# 100x75_BOB.net
KiCad netlist of a schematic drawn in EAGLE
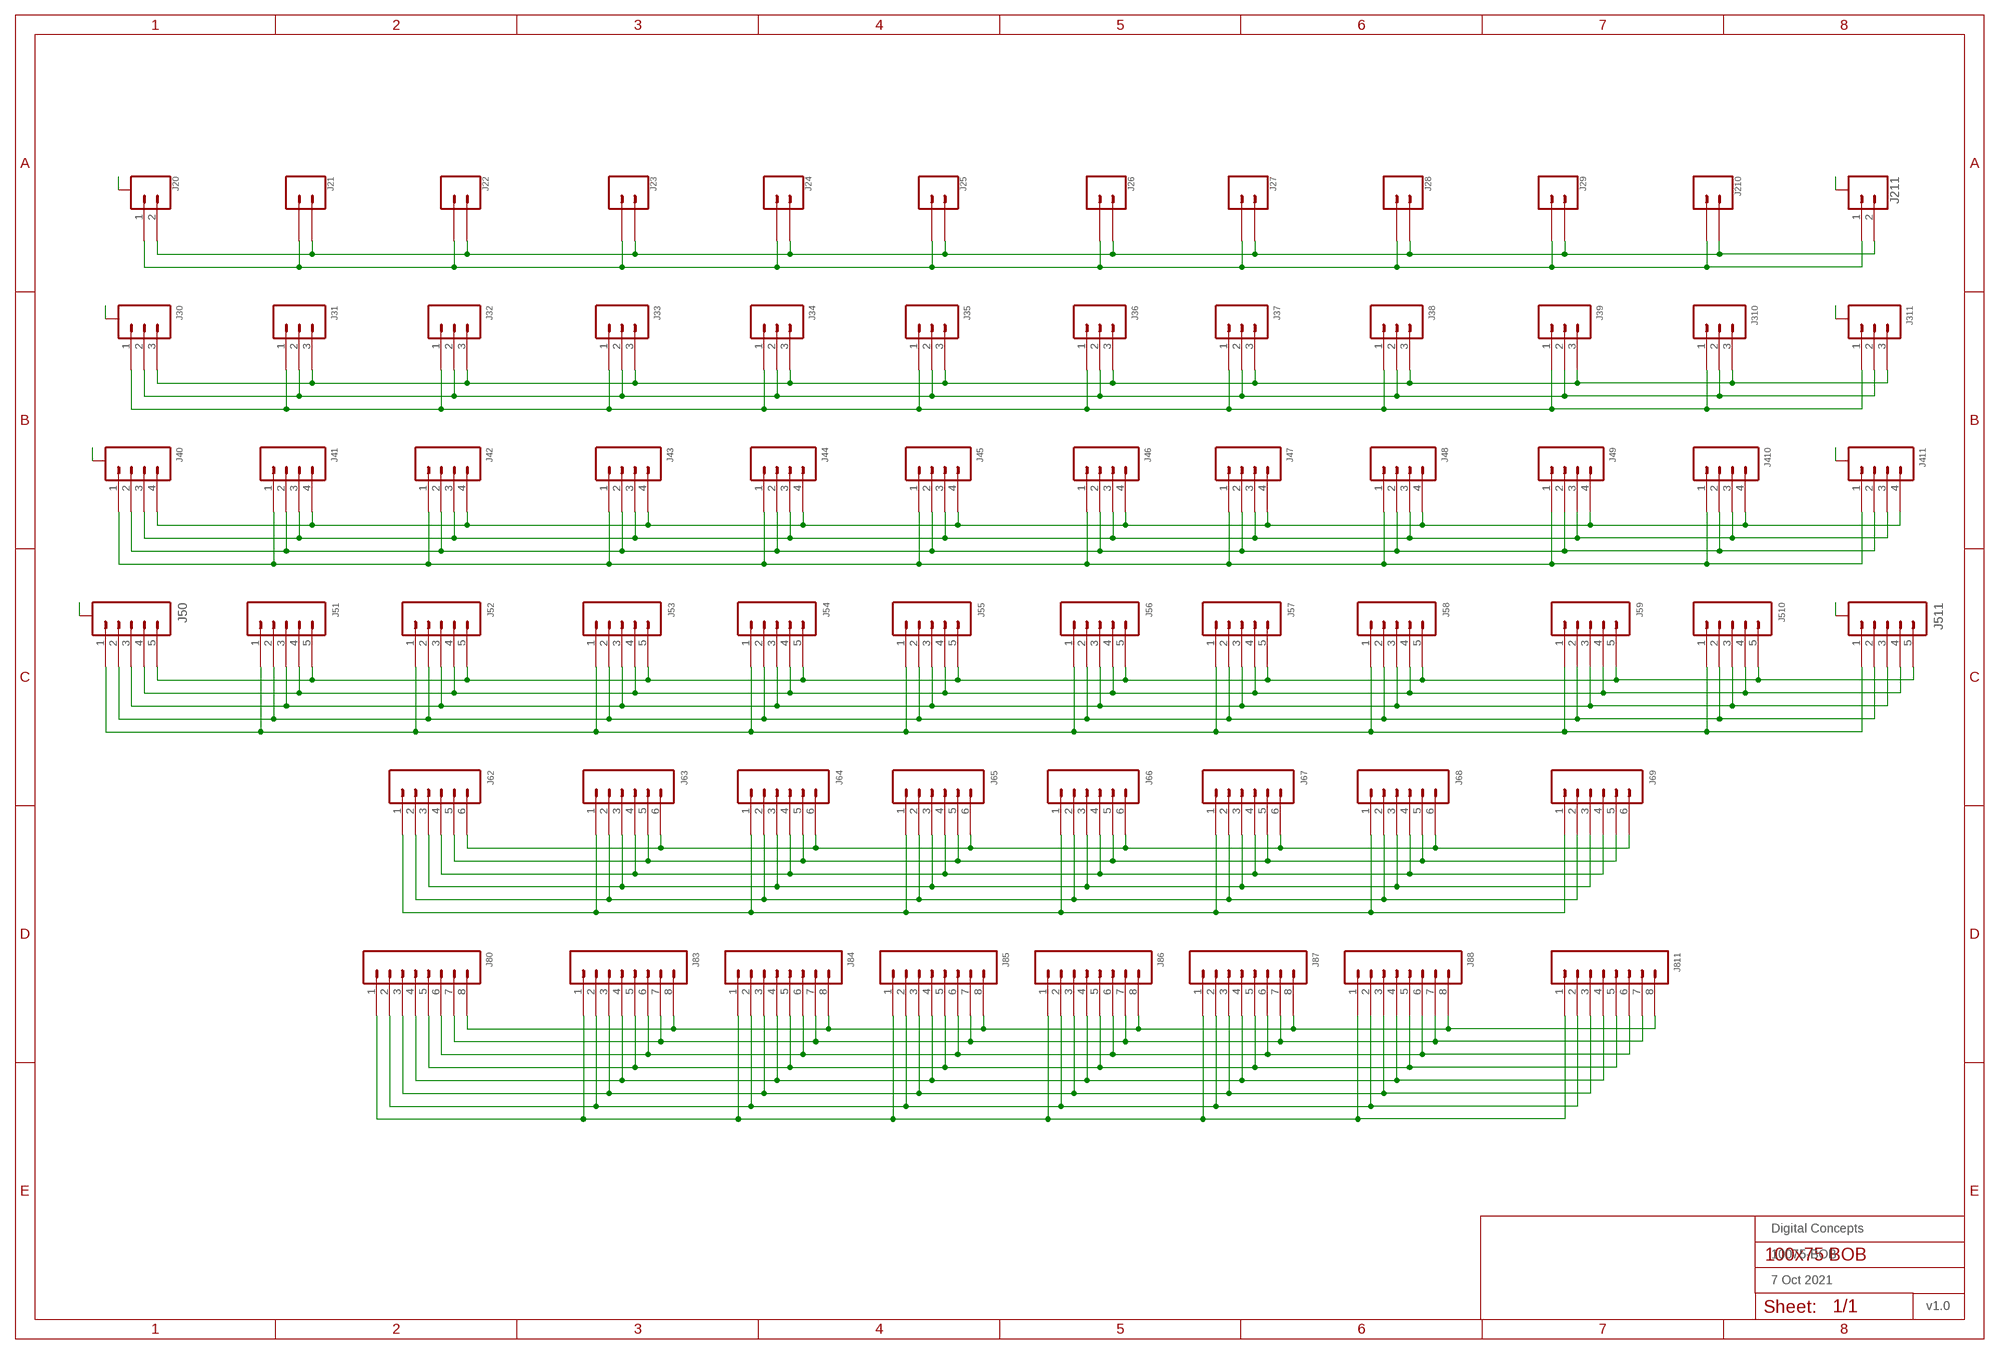
[diagram p0: schematic, sheet 1]

(export (version "E")
  (design (tool "Eeschema 10.0.6"))
  (components
    (comp (ref "J20")
      (value "JST-SH1.0-2-SMD-VERTICAL")
      (footprint "eagle-import:JST-SH1.0-2-VERTICAL")
      (libsource (lib "eagle-import") (part "JST-SH1.0-2-SMD-VERTICAL"))
    )
    (comp (ref "J21")
      (value "JST-GH1.25-2-VERTICAL")
      (footprint "eagle-import:JST-GH1.25-2-VERTICAL")
      (libsource (lib "eagle-import") (part "JST-GH1.25-2-VERTICAL"))
    )
    (comp (ref "J22")
      (value "JST-PH2.0-2-VERTICAL")
      (footprint "eagle-import:JST-PH2.0-2-VERTICAL")
      (libsource (lib "eagle-import") (part "JST-PH2.0-2-VERTICAL"))
    )
    (comp (ref "J23")
      (value "HEADER-1X2-GENERIC")
      (footprint "eagle-import:CONN_02-GENERIC")
      (libsource (lib "eagle-import") (part "HEADER-1X2-GENERIC"))
    )
    (comp (ref "J24")
      (value "HEADER-1X2-GENERIC")
      (footprint "eagle-import:CONN_02-GENERIC")
      (libsource (lib "eagle-import") (part "HEADER-1X2-GENERIC"))
    )
    (comp (ref "J25")
      (value "HEADER-1X2-GENERIC")
      (footprint "eagle-import:CONN_02-GENERIC")
      (libsource (lib "eagle-import") (part "HEADER-1X2-GENERIC"))
    )
    (comp (ref "J26")
      (value "HEADER-1X2-GENERIC")
      (footprint "eagle-import:CONN_02-GENERIC")
      (libsource (lib "eagle-import") (part "HEADER-1X2-GENERIC"))
    )
    (comp (ref "J27")
      (value "HEADER-1X2-GENERIC")
      (footprint "eagle-import:CONN_02-GENERIC")
      (libsource (lib "eagle-import") (part "HEADER-1X2-GENERIC"))
    )
    (comp (ref "J28")
      (value "HEADER-1X2-GENERIC")
      (footprint "eagle-import:CONN_02-GENERIC")
      (libsource (lib "eagle-import") (part "HEADER-1X2-GENERIC"))
    )
    (comp (ref "J29")
      (value "JST-PH2.0-2-VERTICAL")
      (footprint "eagle-import:JST-PH2.0-2-VERTICAL")
      (libsource (lib "eagle-import") (part "JST-PH2.0-2-VERTICAL"))
    )
    (comp (ref "J30")
      (value "JST-SH1.0-3-SMD-VERTICAL")
      (footprint "eagle-import:JST-SH1.0-3-VERTICAL")
      (libsource (lib "eagle-import") (part "JST-SH1.0-3-SMD-VERTICAL"))
    )
    (comp (ref "J31")
      (value "JST-GH1.25-3-VERTICAL")
      (footprint "eagle-import:JST-GH1.25-3-VERTICAL")
      (libsource (lib "eagle-import") (part "JST-GH1.25-3-VERTICAL"))
    )
    (comp (ref "J32")
      (value "JST-PH2.0-3-VERTICAL")
      (footprint "eagle-import:JST-PH2.0-3-VERTICAL")
      (libsource (lib "eagle-import") (part "JST-PH2.0-3-VERTICAL"))
    )
    (comp (ref "J33")
      (value "HEADER-1X3-GENERIC")
      (footprint "eagle-import:CONN_03-GENERIC")
      (libsource (lib "eagle-import") (part "HEADER-1X3-GENERIC"))
    )
    (comp (ref "J34")
      (value "HEADER-1X3-GENERIC")
      (footprint "eagle-import:CONN_03-GENERIC")
      (libsource (lib "eagle-import") (part "HEADER-1X3-GENERIC"))
    )
    (comp (ref "J35")
      (value "HEADER-1X3-GENERIC")
      (footprint "eagle-import:CONN_03-GENERIC")
      (libsource (lib "eagle-import") (part "HEADER-1X3-GENERIC"))
    )
    (comp (ref "J36")
      (value "HEADER-1X3-GENERIC")
      (footprint "eagle-import:CONN_03-GENERIC")
      (libsource (lib "eagle-import") (part "HEADER-1X3-GENERIC"))
    )
    (comp (ref "J37")
      (value "HEADER-1X3-GENERIC")
      (footprint "eagle-import:CONN_03-GENERIC")
      (libsource (lib "eagle-import") (part "HEADER-1X3-GENERIC"))
    )
    (comp (ref "J38")
      (value "HEADER-1X3-GENERIC")
      (footprint "eagle-import:CONN_03-GENERIC")
      (libsource (lib "eagle-import") (part "HEADER-1X3-GENERIC"))
    )
    (comp (ref "J39")
      (value "JST-PH2.0-3-VERTICAL")
      (footprint "eagle-import:JST-PH2.0-3-VERTICAL")
      (libsource (lib "eagle-import") (part "JST-PH2.0-3-VERTICAL"))
    )
    (comp (ref "J40")
      (value "JST-SH1.0-4-SMD-VERTICAL")
      (footprint "eagle-import:JST-SH1.0-4-VERTICAL")
      (libsource (lib "eagle-import") (part "JST-SH1.0-4-SMD-VERTICAL"))
    )
    (comp (ref "J41")
      (value "JST-GH1.25-4-VERTICAL")
      (footprint "eagle-import:JST-GH1.25-4-VERTICAL")
      (libsource (lib "eagle-import") (part "JST-GH1.25-4-VERTICAL"))
    )
    (comp (ref "J42")
      (value "JST-PH2.0-4-VERTICAL")
      (footprint "eagle-import:JST-PH2.0-4-VERTICAL")
      (libsource (lib "eagle-import") (part "JST-PH2.0-4-VERTICAL"))
    )
    (comp (ref "J43")
      (value "HEADER-1X4-GENERIC")
      (footprint "eagle-import:CONN_04-GENERIC")
      (libsource (lib "eagle-import") (part "HEADER-1X4-GENERIC"))
    )
    (comp (ref "J44")
      (value "HEADER-1X4-GENERIC")
      (footprint "eagle-import:CONN_04-GENERIC")
      (libsource (lib "eagle-import") (part "HEADER-1X4-GENERIC"))
    )
    (comp (ref "J45")
      (value "HEADER-1X4-GENERIC")
      (footprint "eagle-import:CONN_04-GENERIC")
      (libsource (lib "eagle-import") (part "HEADER-1X4-GENERIC"))
    )
    (comp (ref "J46")
      (value "HEADER-1X4-GENERIC")
      (footprint "eagle-import:CONN_04-GENERIC")
      (libsource (lib "eagle-import") (part "HEADER-1X4-GENERIC"))
    )
    (comp (ref "J47")
      (value "HEADER-1X4-GENERIC")
      (footprint "eagle-import:CONN_04-GENERIC")
      (libsource (lib "eagle-import") (part "HEADER-1X4-GENERIC"))
    )
    (comp (ref "J48")
      (value "HEADER-1X4-GENERIC")
      (footprint "eagle-import:CONN_04-GENERIC")
      (libsource (lib "eagle-import") (part "HEADER-1X4-GENERIC"))
    )
    (comp (ref "J49")
      (value "JST-PH2.0-4-VERTICAL")
      (footprint "eagle-import:JST-PH2.0-4-VERTICAL")
      (libsource (lib "eagle-import") (part "JST-PH2.0-4-VERTICAL"))
    )
    (comp (ref "J50")
      (value "JST-SH1.0-5-SMD-VERTICAL")
      (footprint "eagle-import:JST-SH1.0-5-VERTICAL")
      (libsource (lib "eagle-import") (part "JST-SH1.0-5-SMD-VERTICAL"))
    )
    (comp (ref "J51")
      (value "JST-GH1.25-5-VERTICAL")
      (footprint "eagle-import:JST-GH1.25-5-VERTICAL")
      (libsource (lib "eagle-import") (part "JST-GH1.25-5-VERTICAL"))
    )
    (comp (ref "J52")
      (value "JST-PH2.0-5-VERTICAL")
      (footprint "eagle-import:JST-PH2.0-5-VERTICAL")
      (libsource (lib "eagle-import") (part "JST-PH2.0-5-VERTICAL"))
    )
    (comp (ref "J53")
      (value "HEADER-1X5-GENERIC")
      (footprint "eagle-import:CONN_05-GENERIC")
      (libsource (lib "eagle-import") (part "HEADER-1X5-GENERIC"))
    )
    (comp (ref "J54")
      (value "HEADER-1X5-GENERIC")
      (footprint "eagle-import:CONN_05-GENERIC")
      (libsource (lib "eagle-import") (part "HEADER-1X5-GENERIC"))
    )
    (comp (ref "J55")
      (value "HEADER-1X5-GENERIC")
      (footprint "eagle-import:CONN_05-GENERIC")
      (libsource (lib "eagle-import") (part "HEADER-1X5-GENERIC"))
    )
    (comp (ref "J56")
      (value "HEADER-1X5-GENERIC")
      (footprint "eagle-import:CONN_05-GENERIC")
      (libsource (lib "eagle-import") (part "HEADER-1X5-GENERIC"))
    )
    (comp (ref "J57")
      (value "HEADER-1X5-GENERIC")
      (footprint "eagle-import:CONN_05-GENERIC")
      (libsource (lib "eagle-import") (part "HEADER-1X5-GENERIC"))
    )
    (comp (ref "J58")
      (value "HEADER-1X5-GENERIC")
      (footprint "eagle-import:CONN_05-GENERIC")
      (libsource (lib "eagle-import") (part "HEADER-1X5-GENERIC"))
    )
    (comp (ref "J59")
      (value "JST-PH2.0-5-VERTICAL")
      (footprint "eagle-import:JST-PH2.0-5-VERTICAL")
      (libsource (lib "eagle-import") (part "JST-PH2.0-5-VERTICAL"))
    )
    (comp (ref "J62")
      (value "RJ11-6P6C-VERTICAL")
      (footprint "eagle-import:RJ11-6-VERTICAL")
      (libsource (lib "eagle-import") (part "RJ11-6P6C-VERTICAL"))
    )
    (comp (ref "J63")
      (value "HEADER-1X6-GENERIC")
      (footprint "eagle-import:CONN_06-GENERIC")
      (libsource (lib "eagle-import") (part "HEADER-1X6-GENERIC"))
    )
    (comp (ref "J64")
      (value "HEADER-1X6-GENERIC")
      (footprint "eagle-import:CONN_06-GENERIC")
      (libsource (lib "eagle-import") (part "HEADER-1X6-GENERIC"))
    )
    (comp (ref "J65")
      (value "HEADER-1X6-GENERIC")
      (footprint "eagle-import:CONN_06-GENERIC")
      (libsource (lib "eagle-import") (part "HEADER-1X6-GENERIC"))
    )
    (comp (ref "J66")
      (value "HEADER-1X6-GENERIC")
      (footprint "eagle-import:CONN_06-GENERIC")
      (libsource (lib "eagle-import") (part "HEADER-1X6-GENERIC"))
    )
    (comp (ref "J67")
      (value "HEADER-1X6-GENERIC")
      (footprint "eagle-import:CONN_06-GENERIC")
      (libsource (lib "eagle-import") (part "HEADER-1X6-GENERIC"))
    )
    (comp (ref "J68")
      (value "HEADER-1X6-GENERIC")
      (footprint "eagle-import:CONN_06-GENERIC")
      (libsource (lib "eagle-import") (part "HEADER-1X6-GENERIC"))
    )
    (comp (ref "J69")
      (value "RJ11-6P6C-VERTICAL")
      (footprint "eagle-import:RJ11-6-VERTICAL")
      (libsource (lib "eagle-import") (part "RJ11-6P6C-VERTICAL"))
    )
    (comp (ref "J80")
      (value "RJ45-8P8C-VERTICAL")
      (footprint "eagle-import:RJ45-VERTICAL")
      (libsource (lib "eagle-import") (part "RJ45-8P8C-VERTICAL"))
    )
    (comp (ref "J83")
      (value "HEADER-1X8-GENERIC")
      (footprint "eagle-import:CONN_08-GENERIC")
      (libsource (lib "eagle-import") (part "HEADER-1X8-GENERIC"))
    )
    (comp (ref "J84")
      (value "HEADER-1X8-GENERIC")
      (footprint "eagle-import:CONN_08-GENERIC")
      (libsource (lib "eagle-import") (part "HEADER-1X8-GENERIC"))
    )
    (comp (ref "J85")
      (value "HEADER-1X8-GENERIC")
      (footprint "eagle-import:CONN_08-GENERIC")
      (libsource (lib "eagle-import") (part "HEADER-1X8-GENERIC"))
    )
    (comp (ref "J86")
      (value "HEADER-1X8-GENERIC")
      (footprint "eagle-import:CONN_08-GENERIC")
      (libsource (lib "eagle-import") (part "HEADER-1X8-GENERIC"))
    )
    (comp (ref "J87")
      (value "HEADER-1X8-GENERIC")
      (footprint "eagle-import:CONN_08-GENERIC")
      (libsource (lib "eagle-import") (part "HEADER-1X8-GENERIC"))
    )
    (comp (ref "J88")
      (value "HEADER-1X8-GENERIC")
      (footprint "eagle-import:CONN_08-GENERIC")
      (libsource (lib "eagle-import") (part "HEADER-1X8-GENERIC"))
    )
    (comp (ref "J210")
      (value "JST-GH1.25-2-VERTICAL")
      (footprint "eagle-import:JST-GH1.25-2-VERTICAL")
      (libsource (lib "eagle-import") (part "JST-GH1.25-2-VERTICAL"))
    )
    (comp (ref "J211")
      (value "JST-SH1.0-2-SMD-VERTICAL")
      (footprint "eagle-import:JST-SH1.0-2-VERTICAL")
      (libsource (lib "eagle-import") (part "JST-SH1.0-2-SMD-VERTICAL"))
    )
    (comp (ref "J310")
      (value "JST-GH1.25-3-VERTICAL")
      (footprint "eagle-import:JST-GH1.25-3-VERTICAL")
      (libsource (lib "eagle-import") (part "JST-GH1.25-3-VERTICAL"))
    )
    (comp (ref "J311")
      (value "JST-SH1.0-3-SMD-VERTICAL")
      (footprint "eagle-import:JST-SH1.0-3-VERTICAL")
      (libsource (lib "eagle-import") (part "JST-SH1.0-3-SMD-VERTICAL"))
    )
    (comp (ref "J410")
      (value "JST-GH1.25-4-VERTICAL")
      (footprint "eagle-import:JST-GH1.25-4-VERTICAL")
      (libsource (lib "eagle-import") (part "JST-GH1.25-4-VERTICAL"))
    )
    (comp (ref "J411")
      (value "JST-SH1.0-4-SMD-VERTICAL")
      (footprint "eagle-import:JST-SH1.0-4-VERTICAL")
      (libsource (lib "eagle-import") (part "JST-SH1.0-4-SMD-VERTICAL"))
    )
    (comp (ref "J510")
      (value "JST-GH1.25-5-VERTICAL")
      (footprint "eagle-import:JST-GH1.25-5-VERTICAL")
      (libsource (lib "eagle-import") (part "JST-GH1.25-5-VERTICAL"))
    )
    (comp (ref "J511")
      (value "JST-SH1.0-5-SMD-VERTICAL")
      (footprint "eagle-import:JST-SH1.0-5-VERTICAL")
      (libsource (lib "eagle-import") (part "JST-SH1.0-5-SMD-VERTICAL"))
    )
    (comp (ref "J811")
      (value "RJ45-8P8C-VERTICAL")
      (footprint "eagle-import:RJ45-VERTICAL")
      (libsource (lib "eagle-import") (part "RJ45-8P8C-VERTICAL"))
    )
  )
  (nets
    (net (code "1") (name "/A") (class "Default")
      (node (ref "J20") (pin "A@1") (pinfunction "A_A@1") (pintype "power_in"))
      (node (ref "J20") (pin "A@2") (pinfunction "A_A@2") (pintype "power_in"))
      (node (ref "J211") (pin "A@1") (pinfunction "A_A@1") (pintype "power_in"))
      (node (ref "J211") (pin "A@2") (pinfunction "A_A@2") (pintype "power_in"))
      (node (ref "J30") (pin "A@1") (pinfunction "A_A@1") (pintype "power_in"))
      (node (ref "J30") (pin "A@3") (pinfunction "A_A@3") (pintype "power_in"))
      (node (ref "J311") (pin "A@1") (pinfunction "A_A@1") (pintype "power_in"))
      (node (ref "J311") (pin "A@3") (pinfunction "A_A@3") (pintype "power_in"))
      (node (ref "J40") (pin "A@1") (pinfunction "A_A@1") (pintype "power_in"))
      (node (ref "J40") (pin "A@4") (pinfunction "A_A@4") (pintype "power_in"))
      (node (ref "J411") (pin "A@1") (pinfunction "A_A@1") (pintype "power_in"))
      (node (ref "J411") (pin "A@4") (pinfunction "A_A@4") (pintype "power_in"))
      (node (ref "J50") (pin "A@1") (pinfunction "A_A@1") (pintype "power_in"))
      (node (ref "J50") (pin "A@5") (pinfunction "A_A@5") (pintype "power_in"))
      (node (ref "J511") (pin "A@1") (pinfunction "A_A@1") (pintype "power_in"))
      (node (ref "J511") (pin "A@5") (pinfunction "A_A@5") (pintype "power_in"))
    )
    (net (code "2") (name "Net-(J20-Pad1)") (class "Default")
      (node (ref "J20") (pin "1") (pinfunction "1_1") (pintype "passive"))
      (node (ref "J21") (pin "1") (pinfunction "1_1") (pintype "passive"))
      (node (ref "J210") (pin "1") (pinfunction "1_1") (pintype "passive"))
      (node (ref "J211") (pin "1") (pinfunction "1_1") (pintype "passive"))
      (node (ref "J22") (pin "1") (pinfunction "1_1") (pintype "passive"))
      (node (ref "J23") (pin "1") (pinfunction "1_1") (pintype "passive"))
      (node (ref "J24") (pin "1") (pinfunction "1_1") (pintype "passive"))
      (node (ref "J25") (pin "1") (pinfunction "1_1") (pintype "passive"))
      (node (ref "J26") (pin "1") (pinfunction "1_1") (pintype "passive"))
      (node (ref "J27") (pin "1") (pinfunction "1_1") (pintype "passive"))
      (node (ref "J28") (pin "1") (pinfunction "1_1") (pintype "passive"))
      (node (ref "J29") (pin "1") (pinfunction "1_1") (pintype "passive"))
    )
    (net (code "3") (name "Net-(J20-Pad2)") (class "Default")
      (node (ref "J20") (pin "2") (pinfunction "2_2") (pintype "passive"))
      (node (ref "J21") (pin "2") (pinfunction "2_2") (pintype "passive"))
      (node (ref "J210") (pin "2") (pinfunction "2_2") (pintype "passive"))
      (node (ref "J211") (pin "2") (pinfunction "2_2") (pintype "passive"))
      (node (ref "J22") (pin "2") (pinfunction "2_2") (pintype "passive"))
      (node (ref "J23") (pin "2") (pinfunction "2_2") (pintype "passive"))
      (node (ref "J24") (pin "2") (pinfunction "2_2") (pintype "passive"))
      (node (ref "J25") (pin "2") (pinfunction "2_2") (pintype "passive"))
      (node (ref "J26") (pin "2") (pinfunction "2_2") (pintype "passive"))
      (node (ref "J27") (pin "2") (pinfunction "2_2") (pintype "passive"))
      (node (ref "J28") (pin "2") (pinfunction "2_2") (pintype "passive"))
      (node (ref "J29") (pin "2") (pinfunction "2_2") (pintype "passive"))
    )
    (net (code "4") (name "Net-(J30-Pad1)") (class "Default")
      (node (ref "J30") (pin "1") (pinfunction "1_1") (pintype "passive"))
      (node (ref "J31") (pin "1") (pinfunction "1_1") (pintype "passive"))
      (node (ref "J310") (pin "1") (pinfunction "1_1") (pintype "passive"))
      (node (ref "J311") (pin "1") (pinfunction "1_1") (pintype "passive"))
      (node (ref "J32") (pin "1") (pinfunction "1_1") (pintype "passive"))
      (node (ref "J33") (pin "1") (pinfunction "1_1") (pintype "passive"))
      (node (ref "J34") (pin "1") (pinfunction "1_1") (pintype "passive"))
      (node (ref "J35") (pin "1") (pinfunction "1_1") (pintype "passive"))
      (node (ref "J36") (pin "1") (pinfunction "1_1") (pintype "passive"))
      (node (ref "J37") (pin "1") (pinfunction "1_1") (pintype "passive"))
      (node (ref "J38") (pin "1") (pinfunction "1_1") (pintype "passive"))
      (node (ref "J39") (pin "1") (pinfunction "1_1") (pintype "passive"))
    )
    (net (code "5") (name "Net-(J30-Pad2)") (class "Default")
      (node (ref "J30") (pin "2") (pinfunction "2_2") (pintype "passive"))
      (node (ref "J31") (pin "2") (pinfunction "2_2") (pintype "passive"))
      (node (ref "J310") (pin "2") (pinfunction "2_2") (pintype "passive"))
      (node (ref "J311") (pin "2") (pinfunction "2_2") (pintype "passive"))
      (node (ref "J32") (pin "2") (pinfunction "2_2") (pintype "passive"))
      (node (ref "J33") (pin "2") (pinfunction "2_2") (pintype "passive"))
      (node (ref "J34") (pin "2") (pinfunction "2_2") (pintype "passive"))
      (node (ref "J35") (pin "2") (pinfunction "2_2") (pintype "passive"))
      (node (ref "J36") (pin "2") (pinfunction "2_2") (pintype "passive"))
      (node (ref "J37") (pin "2") (pinfunction "2_2") (pintype "passive"))
      (node (ref "J38") (pin "2") (pinfunction "2_2") (pintype "passive"))
      (node (ref "J39") (pin "2") (pinfunction "2_2") (pintype "passive"))
    )
    (net (code "6") (name "Net-(J30-Pad3)") (class "Default")
      (node (ref "J30") (pin "3") (pinfunction "3_3") (pintype "passive"))
      (node (ref "J31") (pin "3") (pinfunction "3_3") (pintype "passive"))
      (node (ref "J310") (pin "3") (pinfunction "3_3") (pintype "passive"))
      (node (ref "J311") (pin "3") (pinfunction "3_3") (pintype "passive"))
      (node (ref "J32") (pin "3") (pinfunction "3_3") (pintype "passive"))
      (node (ref "J33") (pin "3") (pinfunction "3_3") (pintype "passive"))
      (node (ref "J34") (pin "3") (pinfunction "3_3") (pintype "passive"))
      (node (ref "J35") (pin "3") (pinfunction "3_3") (pintype "passive"))
      (node (ref "J36") (pin "3") (pinfunction "3_3") (pintype "passive"))
      (node (ref "J37") (pin "3") (pinfunction "3_3") (pintype "passive"))
      (node (ref "J38") (pin "3") (pinfunction "3_3") (pintype "passive"))
      (node (ref "J39") (pin "3") (pinfunction "3_3") (pintype "passive"))
    )
    (net (code "7") (name "Net-(J40-Pad1)") (class "Default")
      (node (ref "J40") (pin "1") (pinfunction "1_1") (pintype "passive"))
      (node (ref "J41") (pin "1") (pinfunction "1_1") (pintype "passive"))
      (node (ref "J410") (pin "1") (pinfunction "1_1") (pintype "passive"))
      (node (ref "J411") (pin "1") (pinfunction "1_1") (pintype "passive"))
      (node (ref "J42") (pin "1") (pinfunction "1_1") (pintype "passive"))
      (node (ref "J43") (pin "1") (pinfunction "1_1") (pintype "passive"))
      (node (ref "J44") (pin "1") (pinfunction "1_1") (pintype "passive"))
      (node (ref "J45") (pin "1") (pinfunction "1_1") (pintype "passive"))
      (node (ref "J46") (pin "1") (pinfunction "1_1") (pintype "passive"))
      (node (ref "J47") (pin "1") (pinfunction "1_1") (pintype "passive"))
      (node (ref "J48") (pin "1") (pinfunction "1_1") (pintype "passive"))
      (node (ref "J49") (pin "1") (pinfunction "1_1") (pintype "passive"))
    )
    (net (code "8") (name "Net-(J40-Pad2)") (class "Default")
      (node (ref "J40") (pin "2") (pinfunction "2_2") (pintype "passive"))
      (node (ref "J41") (pin "2") (pinfunction "2_2") (pintype "passive"))
      (node (ref "J410") (pin "2") (pinfunction "2_2") (pintype "passive"))
      (node (ref "J411") (pin "2") (pinfunction "2_2") (pintype "passive"))
      (node (ref "J42") (pin "2") (pinfunction "2_2") (pintype "passive"))
      (node (ref "J43") (pin "2") (pinfunction "2_2") (pintype "passive"))
      (node (ref "J44") (pin "2") (pinfunction "2_2") (pintype "passive"))
      (node (ref "J45") (pin "2") (pinfunction "2_2") (pintype "passive"))
      (node (ref "J46") (pin "2") (pinfunction "2_2") (pintype "passive"))
      (node (ref "J47") (pin "2") (pinfunction "2_2") (pintype "passive"))
      (node (ref "J48") (pin "2") (pinfunction "2_2") (pintype "passive"))
      (node (ref "J49") (pin "2") (pinfunction "2_2") (pintype "passive"))
    )
    (net (code "9") (name "Net-(J40-Pad3)") (class "Default")
      (node (ref "J40") (pin "3") (pinfunction "3_3") (pintype "passive"))
      (node (ref "J41") (pin "3") (pinfunction "3_3") (pintype "passive"))
      (node (ref "J410") (pin "3") (pinfunction "3_3") (pintype "passive"))
      (node (ref "J411") (pin "3") (pinfunction "3_3") (pintype "passive"))
      (node (ref "J42") (pin "3") (pinfunction "3_3") (pintype "passive"))
      (node (ref "J43") (pin "3") (pinfunction "3_3") (pintype "passive"))
      (node (ref "J44") (pin "3") (pinfunction "3_3") (pintype "passive"))
      (node (ref "J45") (pin "3") (pinfunction "3_3") (pintype "passive"))
      (node (ref "J46") (pin "3") (pinfunction "3_3") (pintype "passive"))
      (node (ref "J47") (pin "3") (pinfunction "3_3") (pintype "passive"))
      (node (ref "J48") (pin "3") (pinfunction "3_3") (pintype "passive"))
      (node (ref "J49") (pin "3") (pinfunction "3_3") (pintype "passive"))
    )
    (net (code "10") (name "Net-(J40-Pad4)") (class "Default")
      (node (ref "J40") (pin "4") (pinfunction "4_4") (pintype "passive"))
      (node (ref "J41") (pin "4") (pinfunction "4_4") (pintype "passive"))
      (node (ref "J410") (pin "4") (pinfunction "4_4") (pintype "passive"))
      (node (ref "J411") (pin "4") (pinfunction "4_4") (pintype "passive"))
      (node (ref "J42") (pin "4") (pinfunction "4_4") (pintype "passive"))
      (node (ref "J43") (pin "4") (pinfunction "4_4") (pintype "passive"))
      (node (ref "J44") (pin "4") (pinfunction "4_4") (pintype "passive"))
      (node (ref "J45") (pin "4") (pinfunction "4_4") (pintype "passive"))
      (node (ref "J46") (pin "4") (pinfunction "4_4") (pintype "passive"))
      (node (ref "J47") (pin "4") (pinfunction "4_4") (pintype "passive"))
      (node (ref "J48") (pin "4") (pinfunction "4_4") (pintype "passive"))
      (node (ref "J49") (pin "4") (pinfunction "4_4") (pintype "passive"))
    )
    (net (code "11") (name "Net-(J50-Pad1)") (class "Default")
      (node (ref "J50") (pin "1") (pinfunction "1_1") (pintype "passive"))
      (node (ref "J51") (pin "1") (pinfunction "1_1") (pintype "passive"))
      (node (ref "J510") (pin "1") (pinfunction "1_1") (pintype "passive"))
      (node (ref "J511") (pin "1") (pinfunction "1_1") (pintype "passive"))
      (node (ref "J52") (pin "1") (pinfunction "1_1") (pintype "passive"))
      (node (ref "J53") (pin "1") (pinfunction "1_1") (pintype "passive"))
      (node (ref "J54") (pin "1") (pinfunction "1_1") (pintype "passive"))
      (node (ref "J55") (pin "1") (pinfunction "1_1") (pintype "passive"))
      (node (ref "J56") (pin "1") (pinfunction "1_1") (pintype "passive"))
      (node (ref "J57") (pin "1") (pinfunction "1_1") (pintype "passive"))
      (node (ref "J58") (pin "1") (pinfunction "1_1") (pintype "passive"))
      (node (ref "J59") (pin "1") (pinfunction "1_1") (pintype "passive"))
    )
    (net (code "12") (name "Net-(J50-Pad2)") (class "Default")
      (node (ref "J50") (pin "2") (pinfunction "2_2") (pintype "passive"))
      (node (ref "J51") (pin "2") (pinfunction "2_2") (pintype "passive"))
      (node (ref "J510") (pin "2") (pinfunction "2_2") (pintype "passive"))
      (node (ref "J511") (pin "2") (pinfunction "2_2") (pintype "passive"))
      (node (ref "J52") (pin "2") (pinfunction "2_2") (pintype "passive"))
      (node (ref "J53") (pin "2") (pinfunction "2_2") (pintype "passive"))
      (node (ref "J54") (pin "2") (pinfunction "2_2") (pintype "passive"))
      (node (ref "J55") (pin "2") (pinfunction "2_2") (pintype "passive"))
      (node (ref "J56") (pin "2") (pinfunction "2_2") (pintype "passive"))
      (node (ref "J57") (pin "2") (pinfunction "2_2") (pintype "passive"))
      (node (ref "J58") (pin "2") (pinfunction "2_2") (pintype "passive"))
      (node (ref "J59") (pin "2") (pinfunction "2_2") (pintype "passive"))
    )
    (net (code "13") (name "Net-(J50-Pad3)") (class "Default")
      (node (ref "J50") (pin "3") (pinfunction "3_3") (pintype "passive"))
      (node (ref "J51") (pin "3") (pinfunction "3_3") (pintype "passive"))
      (node (ref "J510") (pin "3") (pinfunction "3_3") (pintype "passive"))
      (node (ref "J511") (pin "3") (pinfunction "3_3") (pintype "passive"))
      (node (ref "J52") (pin "3") (pinfunction "3_3") (pintype "passive"))
      (node (ref "J53") (pin "3") (pinfunction "3_3") (pintype "passive"))
      (node (ref "J54") (pin "3") (pinfunction "3_3") (pintype "passive"))
      (node (ref "J55") (pin "3") (pinfunction "3_3") (pintype "passive"))
      (node (ref "J56") (pin "3") (pinfunction "3_3") (pintype "passive"))
      (node (ref "J57") (pin "3") (pinfunction "3_3") (pintype "passive"))
      (node (ref "J58") (pin "3") (pinfunction "3_3") (pintype "passive"))
      (node (ref "J59") (pin "3") (pinfunction "3_3") (pintype "passive"))
    )
    (net (code "14") (name "Net-(J50-Pad4)") (class "Default")
      (node (ref "J50") (pin "4") (pinfunction "4_4") (pintype "passive"))
      (node (ref "J51") (pin "4") (pinfunction "4_4") (pintype "passive"))
      (node (ref "J510") (pin "4") (pinfunction "4_4") (pintype "passive"))
      (node (ref "J511") (pin "4") (pinfunction "4_4") (pintype "passive"))
      (node (ref "J52") (pin "4") (pinfunction "4_4") (pintype "passive"))
      (node (ref "J53") (pin "4") (pinfunction "4_4") (pintype "passive"))
      (node (ref "J54") (pin "4") (pinfunction "4_4") (pintype "passive"))
      (node (ref "J55") (pin "4") (pinfunction "4_4") (pintype "passive"))
      (node (ref "J56") (pin "4") (pinfunction "4_4") (pintype "passive"))
      (node (ref "J57") (pin "4") (pinfunction "4_4") (pintype "passive"))
      (node (ref "J58") (pin "4") (pinfunction "4_4") (pintype "passive"))
      (node (ref "J59") (pin "4") (pinfunction "4_4") (pintype "passive"))
    )
    (net (code "15") (name "Net-(J50-Pad5)") (class "Default")
      (node (ref "J50") (pin "5") (pinfunction "5_5") (pintype "passive"))
      (node (ref "J51") (pin "5") (pinfunction "5_5") (pintype "passive"))
      (node (ref "J510") (pin "5") (pinfunction "5_5") (pintype "passive"))
      (node (ref "J511") (pin "5") (pinfunction "5_5") (pintype "passive"))
      (node (ref "J52") (pin "5") (pinfunction "5_5") (pintype "passive"))
      (node (ref "J53") (pin "5") (pinfunction "5_5") (pintype "passive"))
      (node (ref "J54") (pin "5") (pinfunction "5_5") (pintype "passive"))
      (node (ref "J55") (pin "5") (pinfunction "5_5") (pintype "passive"))
      (node (ref "J56") (pin "5") (pinfunction "5_5") (pintype "passive"))
      (node (ref "J57") (pin "5") (pinfunction "5_5") (pintype "passive"))
      (node (ref "J58") (pin "5") (pinfunction "5_5") (pintype "passive"))
      (node (ref "J59") (pin "5") (pinfunction "5_5") (pintype "passive"))
    )
    (net (code "16") (name "Net-(J62-Pad1)") (class "Default")
      (node (ref "J62") (pin "1") (pinfunction "1_1") (pintype "passive"))
      (node (ref "J63") (pin "1") (pinfunction "1_1") (pintype "passive"))
      (node (ref "J64") (pin "1") (pinfunction "1_1") (pintype "passive"))
      (node (ref "J65") (pin "1") (pinfunction "1_1") (pintype "passive"))
      (node (ref "J66") (pin "1") (pinfunction "1_1") (pintype "passive"))
      (node (ref "J67") (pin "1") (pinfunction "1_1") (pintype "passive"))
      (node (ref "J68") (pin "1") (pinfunction "1_1") (pintype "passive"))
      (node (ref "J69") (pin "1") (pinfunction "1_1") (pintype "passive"))
    )
    (net (code "17") (name "Net-(J62-Pad2)") (class "Default")
      (node (ref "J62") (pin "2") (pinfunction "2_2") (pintype "passive"))
      (node (ref "J63") (pin "2") (pinfunction "2_2") (pintype "passive"))
      (node (ref "J64") (pin "2") (pinfunction "2_2") (pintype "passive"))
      (node (ref "J65") (pin "2") (pinfunction "2_2") (pintype "passive"))
      (node (ref "J66") (pin "2") (pinfunction "2_2") (pintype "passive"))
      (node (ref "J67") (pin "2") (pinfunction "2_2") (pintype "passive"))
      (node (ref "J68") (pin "2") (pinfunction "2_2") (pintype "passive"))
      (node (ref "J69") (pin "2") (pinfunction "2_2") (pintype "passive"))
    )
    (net (code "18") (name "Net-(J62-Pad3)") (class "Default")
      (node (ref "J62") (pin "3") (pinfunction "3_3") (pintype "passive"))
      (node (ref "J63") (pin "3") (pinfunction "3_3") (pintype "passive"))
      (node (ref "J64") (pin "3") (pinfunction "3_3") (pintype "passive"))
      (node (ref "J65") (pin "3") (pinfunction "3_3") (pintype "passive"))
      (node (ref "J66") (pin "3") (pinfunction "3_3") (pintype "passive"))
      (node (ref "J67") (pin "3") (pinfunction "3_3") (pintype "passive"))
      (node (ref "J68") (pin "3") (pinfunction "3_3") (pintype "passive"))
      (node (ref "J69") (pin "3") (pinfunction "3_3") (pintype "passive"))
    )
    (net (code "19") (name "Net-(J62-Pad4)") (class "Default")
      (node (ref "J62") (pin "4") (pinfunction "4_4") (pintype "passive"))
      (node (ref "J63") (pin "4") (pinfunction "4_4") (pintype "passive"))
      (node (ref "J64") (pin "4") (pinfunction "4_4") (pintype "passive"))
      (node (ref "J65") (pin "4") (pinfunction "4_4") (pintype "passive"))
      (node (ref "J66") (pin "4") (pinfunction "4_4") (pintype "passive"))
      (node (ref "J67") (pin "4") (pinfunction "4_4") (pintype "passive"))
      (node (ref "J68") (pin "4") (pinfunction "4_4") (pintype "passive"))
      (node (ref "J69") (pin "4") (pinfunction "4_4") (pintype "passive"))
    )
    (net (code "20") (name "Net-(J62-Pad5)") (class "Default")
      (node (ref "J62") (pin "5") (pinfunction "5_5") (pintype "passive"))
      (node (ref "J63") (pin "5") (pinfunction "5_5") (pintype "passive"))
      (node (ref "J64") (pin "5") (pinfunction "5_5") (pintype "passive"))
      (node (ref "J65") (pin "5") (pinfunction "5_5") (pintype "passive"))
      (node (ref "J66") (pin "5") (pinfunction "5_5") (pintype "passive"))
      (node (ref "J67") (pin "5") (pinfunction "5_5") (pintype "passive"))
      (node (ref "J68") (pin "5") (pinfunction "5_5") (pintype "passive"))
      (node (ref "J69") (pin "5") (pinfunction "5_5") (pintype "passive"))
    )
    (net (code "21") (name "Net-(J62-Pad6)") (class "Default")
      (node (ref "J62") (pin "6") (pinfunction "6_6") (pintype "passive"))
      (node (ref "J63") (pin "6") (pinfunction "6_6") (pintype "passive"))
      (node (ref "J64") (pin "6") (pinfunction "6_6") (pintype "passive"))
      (node (ref "J65") (pin "6") (pinfunction "6_6") (pintype "passive"))
      (node (ref "J66") (pin "6") (pinfunction "6_6") (pintype "passive"))
      (node (ref "J67") (pin "6") (pinfunction "6_6") (pintype "passive"))
      (node (ref "J68") (pin "6") (pinfunction "6_6") (pintype "passive"))
      (node (ref "J69") (pin "6") (pinfunction "6_6") (pintype "passive"))
    )
    (net (code "22") (name "Net-(J80-Pad1)") (class "Default")
      (node (ref "J80") (pin "1") (pinfunction "1_1") (pintype "passive"))
      (node (ref "J811") (pin "1") (pinfunction "1_1") (pintype "passive"))
      (node (ref "J83") (pin "1") (pinfunction "1_1") (pintype "passive"))
      (node (ref "J84") (pin "1") (pinfunction "1_1") (pintype "passive"))
      (node (ref "J85") (pin "1") (pinfunction "1_1") (pintype "passive"))
      (node (ref "J86") (pin "1") (pinfunction "1_1") (pintype "passive"))
      (node (ref "J87") (pin "1") (pinfunction "1_1") (pintype "passive"))
      (node (ref "J88") (pin "1") (pinfunction "1_1") (pintype "passive"))
    )
    (net (code "23") (name "Net-(J80-Pad2)") (class "Default")
      (node (ref "J80") (pin "2") (pinfunction "2_2") (pintype "passive"))
      (node (ref "J811") (pin "2") (pinfunction "2_2") (pintype "passive"))
      (node (ref "J83") (pin "2") (pinfunction "2_2") (pintype "passive"))
      (node (ref "J84") (pin "2") (pinfunction "2_2") (pintype "passive"))
      (node (ref "J85") (pin "2") (pinfunction "2_2") (pintype "passive"))
      (node (ref "J86") (pin "2") (pinfunction "2_2") (pintype "passive"))
      (node (ref "J87") (pin "2") (pinfunction "2_2") (pintype "passive"))
      (node (ref "J88") (pin "2") (pinfunction "2_2") (pintype "passive"))
    )
    (net (code "24") (name "Net-(J80-Pad3)") (class "Default")
      (node (ref "J80") (pin "3") (pinfunction "3_3") (pintype "passive"))
      (node (ref "J811") (pin "3") (pinfunction "3_3") (pintype "passive"))
      (node (ref "J83") (pin "3") (pinfunction "3_3") (pintype "passive"))
      (node (ref "J84") (pin "3") (pinfunction "3_3") (pintype "passive"))
      (node (ref "J85") (pin "3") (pinfunction "3_3") (pintype "passive"))
      (node (ref "J86") (pin "3") (pinfunction "3_3") (pintype "passive"))
      (node (ref "J87") (pin "3") (pinfunction "3_3") (pintype "passive"))
      (node (ref "J88") (pin "3") (pinfunction "3_3") (pintype "passive"))
    )
    (net (code "25") (name "Net-(J80-Pad4)") (class "Default")
      (node (ref "J80") (pin "4") (pinfunction "4_4") (pintype "passive"))
      (node (ref "J811") (pin "4") (pinfunction "4_4") (pintype "passive"))
      (node (ref "J83") (pin "4") (pinfunction "4_4") (pintype "passive"))
      (node (ref "J84") (pin "4") (pinfunction "4_4") (pintype "passive"))
      (node (ref "J85") (pin "4") (pinfunction "4_4") (pintype "passive"))
      (node (ref "J86") (pin "4") (pinfunction "4_4") (pintype "passive"))
      (node (ref "J87") (pin "4") (pinfunction "4_4") (pintype "passive"))
      (node (ref "J88") (pin "4") (pinfunction "4_4") (pintype "passive"))
    )
    (net (code "26") (name "Net-(J80-Pad5)") (class "Default")
      (node (ref "J80") (pin "5") (pinfunction "5_5") (pintype "passive"))
      (node (ref "J811") (pin "5") (pinfunction "5_5") (pintype "passive"))
      (node (ref "J83") (pin "5") (pinfunction "5_5") (pintype "passive"))
      (node (ref "J84") (pin "5") (pinfunction "5_5") (pintype "passive"))
      (node (ref "J85") (pin "5") (pinfunction "5_5") (pintype "passive"))
      (node (ref "J86") (pin "5") (pinfunction "5_5") (pintype "passive"))
      (node (ref "J87") (pin "5") (pinfunction "5_5") (pintype "passive"))
      (node (ref "J88") (pin "5") (pinfunction "5_5") (pintype "passive"))
    )
    (net (code "27") (name "Net-(J80-Pad6)") (class "Default")
      (node (ref "J80") (pin "6") (pinfunction "6_6") (pintype "passive"))
      (node (ref "J811") (pin "6") (pinfunction "6_6") (pintype "passive"))
      (node (ref "J83") (pin "6") (pinfunction "6_6") (pintype "passive"))
      (node (ref "J84") (pin "6") (pinfunction "6_6") (pintype "passive"))
      (node (ref "J85") (pin "6") (pinfunction "6_6") (pintype "passive"))
      (node (ref "J86") (pin "6") (pinfunction "6_6") (pintype "passive"))
      (node (ref "J87") (pin "6") (pinfunction "6_6") (pintype "passive"))
      (node (ref "J88") (pin "6") (pinfunction "6_6") (pintype "passive"))
    )
    (net (code "28") (name "Net-(J80-Pad7)") (class "Default")
      (node (ref "J80") (pin "7") (pinfunction "7_7") (pintype "passive"))
      (node (ref "J811") (pin "7") (pinfunction "7_7") (pintype "passive"))
      (node (ref "J83") (pin "7") (pinfunction "7_7") (pintype "passive"))
      (node (ref "J84") (pin "7") (pinfunction "7_7") (pintype "passive"))
      (node (ref "J85") (pin "7") (pinfunction "7_7") (pintype "passive"))
      (node (ref "J86") (pin "7") (pinfunction "7_7") (pintype "passive"))
      (node (ref "J87") (pin "7") (pinfunction "7_7") (pintype "passive"))
      (node (ref "J88") (pin "7") (pinfunction "7_7") (pintype "passive"))
    )
    (net (code "29") (name "Net-(J80-Pad8)") (class "Default")
      (node (ref "J80") (pin "8") (pinfunction "8_8") (pintype "passive"))
      (node (ref "J811") (pin "8") (pinfunction "8_8") (pintype "passive"))
      (node (ref "J83") (pin "8") (pinfunction "8_8") (pintype "passive"))
      (node (ref "J84") (pin "8") (pinfunction "8_8") (pintype "passive"))
      (node (ref "J85") (pin "8") (pinfunction "8_8") (pintype "passive"))
      (node (ref "J86") (pin "8") (pinfunction "8_8") (pintype "passive"))
      (node (ref "J87") (pin "8") (pinfunction "8_8") (pintype "passive"))
      (node (ref "J88") (pin "8") (pinfunction "8_8") (pintype "passive"))
    )
  )
)
